# G717.net
KiCad netlist of a schematic drawn in EAGLE
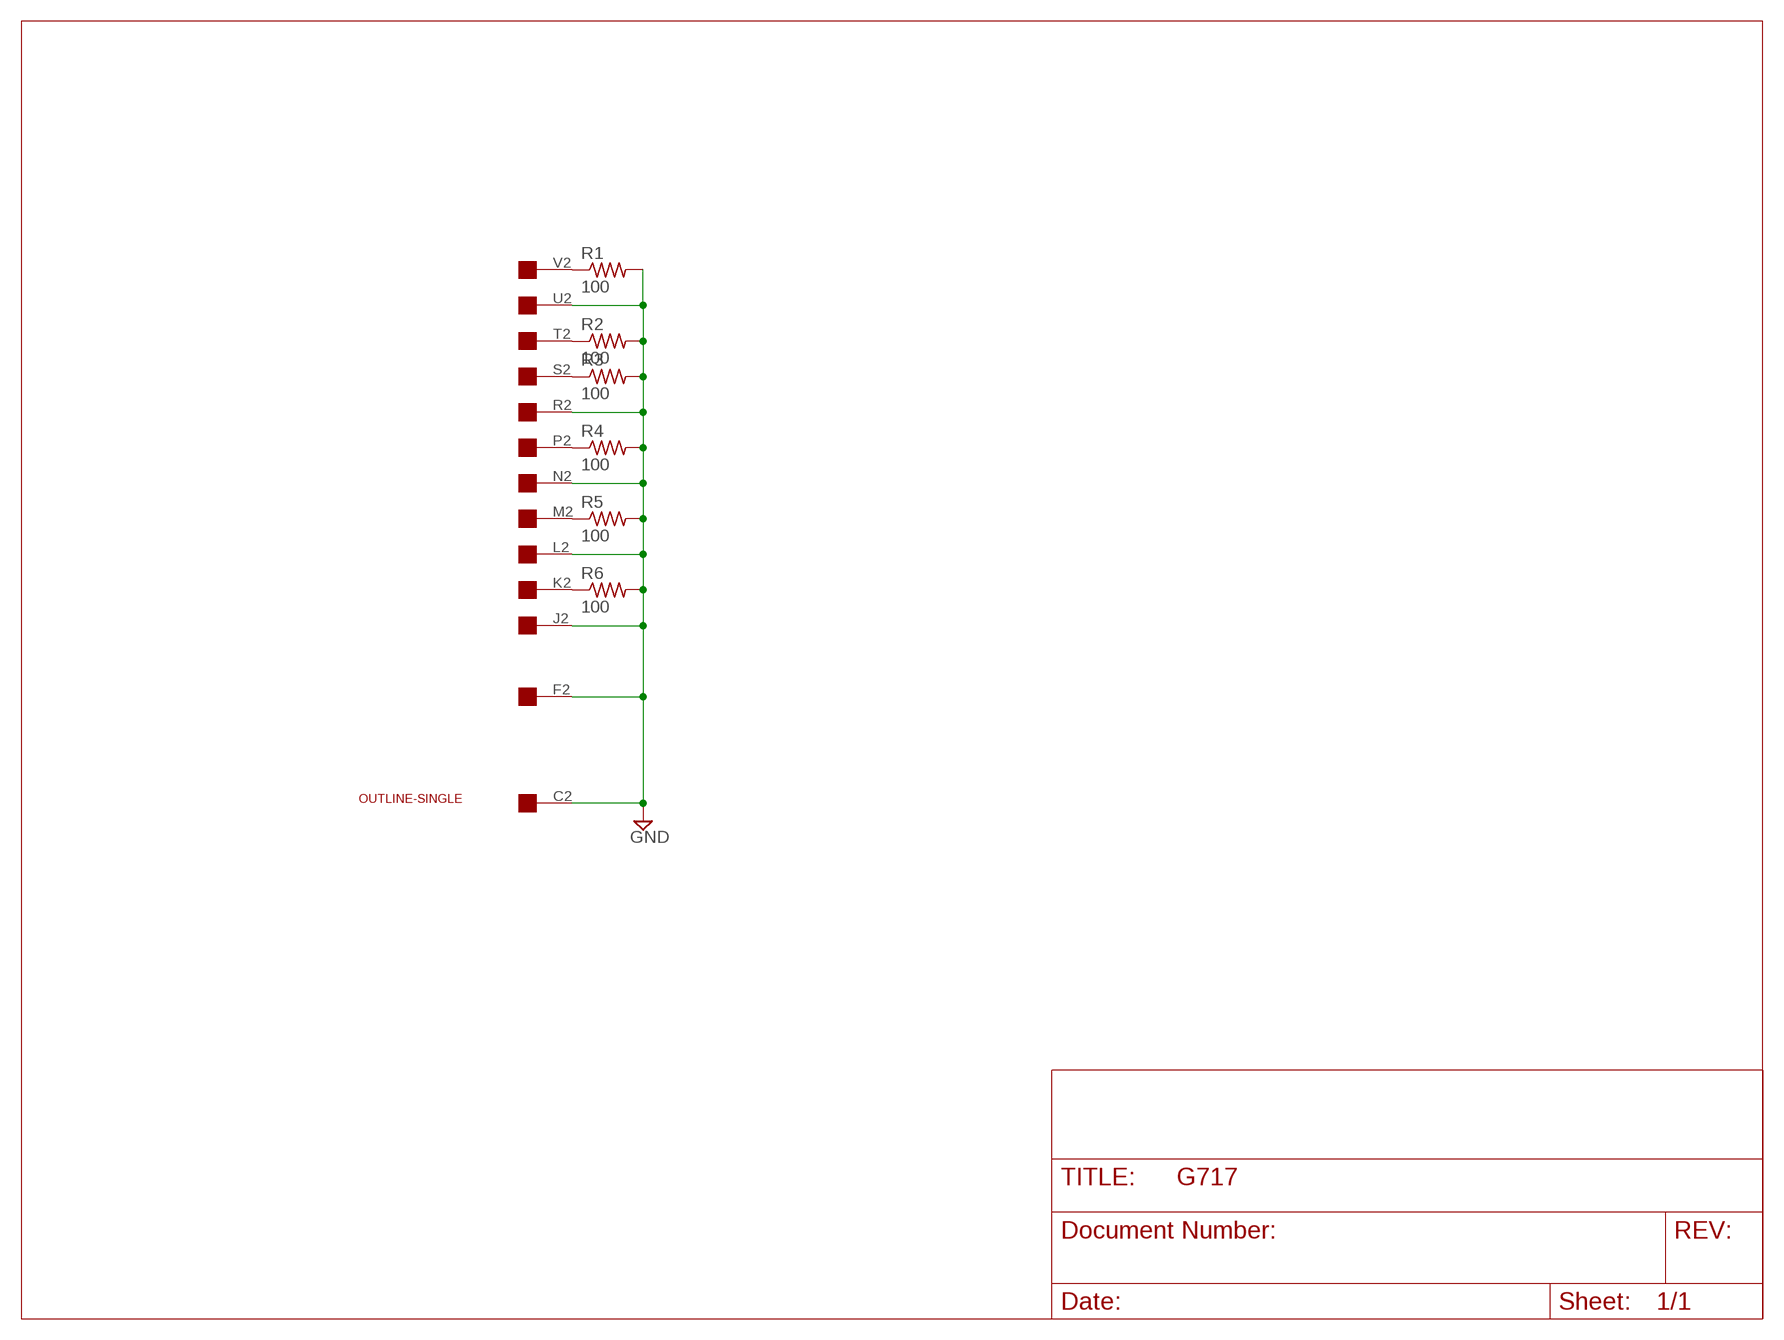
[diagram p0: schematic, sheet 1]

(export (version "E")
  (design (tool "Eeschema 10.0.6"))
  (components
    (comp (ref "R1")
      (value "100")
      (footprint "eagle-import:0207_10")
      (libsource (lib "eagle-import") (part "R-US_0207/10"))
    )
    (comp (ref "R2")
      (value "100")
      (footprint "eagle-import:0207_10")
      (libsource (lib "eagle-import") (part "R-US_0207/10"))
    )
    (comp (ref "R3")
      (value "100")
      (footprint "eagle-import:0207_10")
      (libsource (lib "eagle-import") (part "R-US_0207/10"))
    )
    (comp (ref "R4")
      (value "100")
      (footprint "eagle-import:0207_10")
      (libsource (lib "eagle-import") (part "R-US_0207/10"))
    )
    (comp (ref "R5")
      (value "100")
      (footprint "eagle-import:0207_10")
      (libsource (lib "eagle-import") (part "R-US_0207/10"))
    )
    (comp (ref "R6")
      (value "100")
      (footprint "eagle-import:0207_10")
      (libsource (lib "eagle-import") (part "R-US_0207/10"))
    )
    (comp (ref "U$1")
      (value "OUTLINE-SINGLE")
      (footprint "eagle-import:SINGLE")
      (libsource (lib "eagle-import") (part "OUTLINE-SINGLE"))
    )
    (comp (ref "U$3")
      (value "EDGE-1")
      (footprint "eagle-import:EDGE-CON1")
      (libsource (lib "eagle-import") (part "EDGE-1"))
    )
  )
  (nets
    (net (code "1") (name "GND") (class "Default")
      (node (ref "R1") (pin "2") (pinfunction "2_2") (pintype "passive"))
      (node (ref "R2") (pin "2") (pinfunction "2_2") (pintype "passive"))
      (node (ref "R3") (pin "2") (pinfunction "2_2") (pintype "passive"))
      (node (ref "R4") (pin "2") (pinfunction "2_2") (pintype "passive"))
      (node (ref "R5") (pin "2") (pinfunction "2_2") (pintype "passive"))
      (node (ref "R6") (pin "2") (pinfunction "2_2") (pintype "passive"))
      (node (ref "U$3") (pin "C2") (pinfunction "1_C2") (pintype "bidirectional"))
      (node (ref "U$3") (pin "F2") (pinfunction "1_F2") (pintype "bidirectional"))
      (node (ref "U$3") (pin "J2") (pinfunction "1_J2") (pintype "bidirectional"))
      (node (ref "U$3") (pin "L2") (pinfunction "1_L2") (pintype "bidirectional"))
      (node (ref "U$3") (pin "N2") (pinfunction "1_N2") (pintype "bidirectional"))
      (node (ref "U$3") (pin "R2") (pinfunction "1_R2") (pintype "bidirectional"))
      (node (ref "U$3") (pin "U2") (pinfunction "1_U2") (pintype "bidirectional"))
    )
    (net (code "2") (name "Net-(U$3I-1)") (class "Default")
      (node (ref "R6") (pin "1") (pinfunction "1_1") (pintype "passive"))
      (node (ref "U$3") (pin "K2") (pinfunction "1_K2") (pintype "bidirectional"))
    )
    (net (code "3") (name "Net-(U$3K-1)") (class "Default")
      (node (ref "R5") (pin "1") (pinfunction "1_1") (pintype "passive"))
      (node (ref "U$3") (pin "M2") (pinfunction "1_M2") (pintype "bidirectional"))
    )
    (net (code "4") (name "Net-(U$3M-1)") (class "Default")
      (node (ref "R4") (pin "1") (pinfunction "1_1") (pintype "passive"))
      (node (ref "U$3") (pin "P2") (pinfunction "1_P2") (pintype "bidirectional"))
    )
    (net (code "5") (name "Net-(U$3O-1)") (class "Default")
      (node (ref "R3") (pin "1") (pinfunction "1_1") (pintype "passive"))
      (node (ref "U$3") (pin "S2") (pinfunction "1_S2") (pintype "bidirectional"))
    )
    (net (code "6") (name "Net-(U$3P-1)") (class "Default")
      (node (ref "R2") (pin "1") (pinfunction "1_1") (pintype "passive"))
      (node (ref "U$3") (pin "T2") (pinfunction "1_T2") (pintype "bidirectional"))
    )
    (net (code "7") (name "Net-(U$3R-1)") (class "Default")
      (node (ref "R1") (pin "1") (pinfunction "1_1") (pintype "passive"))
      (node (ref "U$3") (pin "V2") (pinfunction "1_V2") (pintype "bidirectional"))
    )
  )
)
